# CAN_Sheet.net
KiCad netlist of a schematic drawn in Altium Designer
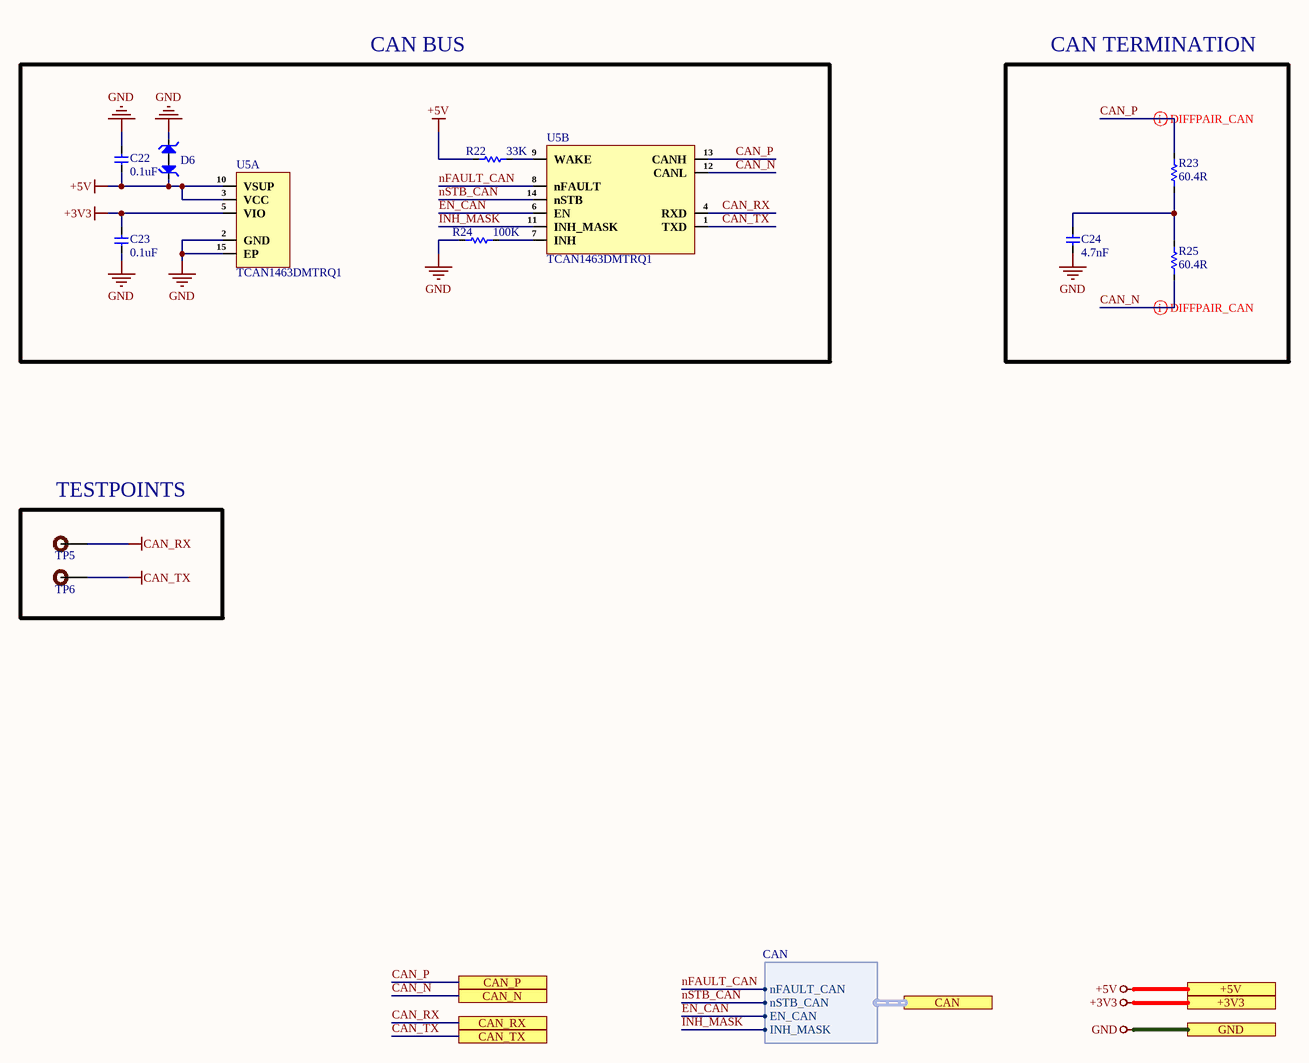
[diagram p0: CAN_Sheet.SchDoc]

(export (version "E")
  (design (tool "Eeschema 10.0.6"))
  (components
    (comp (ref "C22")
      (value "0.1uF")
      (footprint "Cap-0402")
      (description "CAP CER 0.1UF 16V X7R 0402")
      (fields
        (field (name "MANUFACTURER") "Yageo")
        (field (name "MANUFACTURER PART NUMBER") "CC0402JRX7R7BB104")
      )
      (libsource (lib "eSpark Libraries") (part "CC0402JRX7R7BB104"))
    )
    (comp (ref "C23")
      (value "0.1uF")
      (footprint "Cap-0402")
      (description "CAP CER 0.1UF 16V X7R 0402")
      (fields
        (field (name "MANUFACTURER") "Yageo")
        (field (name "MANUFACTURER PART NUMBER") "CC0402JRX7R7BB104")
      )
      (libsource (lib "eSpark Libraries") (part "CC0402JRX7R7BB104"))
    )
    (comp (ref "C24")
      (value "4.7nF")
      (footprint "Cap-0402")
      (description "CAP CER 4700PF 50V X7R 0402")
      (fields
        (field (name "MANUFACTURER") "Yageo")
        (field (name "MANUFACTURER PART NUMBER") "CC0402KRX7R9BB472")
      )
      (libsource (lib "eSpark Libraries") (part "CC0402KRX7R9BB472"))
    )
    (comp (ref "D6")
      (value "PESD5V0H1BSFYL")
      (footprint "DSN0603-2")
      (description "TVS DIODE 5VWM 6.3VC DSN0603-2")
      (fields (field (name "MANUFACTURER") "Nexperia") (field (name "LCSC PART NUMBER") "C477989"))
      (libsource (lib "eSpark Libraries") (part "PESD5V0H1BSFYL"))
    )
    (comp (ref "R22")
      (value "33K")
      (footprint "Res-0402")
      (description "RES 33K OHM 1% 1/16W 0402")
      (fields
        (field (name "MANUFACTURER") "YAGEO")
        (field (name "MANUFACTURER PART NUMBER") "RC0402FR-0733KL")
      )
      (libsource (lib "eSpark Libraries") (part "RC0402FR-0733KL"))
    )
    (comp (ref "R23")
      (value "60.4R")
      (footprint "Res-0603")
      (description "100mW Thick Film Resistors ±100ppm/℃ ±1% 60.4Ω 0603 Chip Resistor - Surface Mount ROHS")
      (fields
        (field (name "MANUFACTURER PART NUMBER") "RTT0360R4FTP")
        (field (name "LCSC PART NUMBER") "C103744")
      )
      (libsource (lib "eSpark Libraries") (part "RTT0360R4FTP"))
    )
    (comp (ref "R24")
      (value "100K")
      (footprint "Res-0402")
      (description "RES 100K OHM 1% 1/16W 0402")
      (fields
        (field (name "MANUFACTURER") "Yageo")
        (field (name "MANUFACTURER PART NUMBER") "RC0402FR-07100KL")
      )
      (libsource (lib "eSpark Libraries") (part "RC0402FR-07100KL"))
    )
    (comp (ref "R25")
      (value "60.4R")
      (footprint "Res-0603")
      (description "100mW Thick Film Resistors ±100ppm/℃ ±1% 60.4Ω 0603 Chip Resistor - Surface Mount ROHS")
      (fields
        (field (name "MANUFACTURER PART NUMBER") "RTT0360R4FTP")
        (field (name "LCSC PART NUMBER") "C103744")
      )
      (libsource (lib "eSpark Libraries") (part "RTT0360R4FTP"))
    )
    (comp (ref "TP5")
      (value "TEST POINT")
      (footprint "Test-point")
      (description "Test Point ON")
      (libsource (lib "eSpark Libraries") (part "TEST POINT"))
    )
    (comp (ref "TP6")
      (value "TEST POINT")
      (footprint "Test-point")
      (description "Test Point ON")
      (libsource (lib "eSpark Libraries") (part "TEST POINT"))
    )
    (comp (ref "U5")
      (value "TCAN1463DMTRQ1")
      (footprint "VSON-14(3x4.5)")
      (description "IC TRANSCEIVER HALF 1/1 14VSON")
      (fields (field (name "MANUFACTURER") "Texas Instruments") (field (name "LCSC PART NUMBER") "C5215823"))
      (libsource (lib "eSpark Libraries") (part "TCAN1463DMTRQ1"))
    )
  )
  (nets
    (net (code "2") (name "+3V3") (class "Default")
      (node (ref "C23") (pin "2") (pinfunction "2_2") (pintype "passive"))
      (node (ref "U5") (pin "5") (pinfunction "VIO_5") (pintype "passive"))
    )
    (net (code "3") (name "+5V") (class "Default")
      (node (ref "C22") (pin "1") (pinfunction "1_1") (pintype "passive"))
      (node (ref "D6") (pin "1") (pinfunction "1_1") (pintype "passive"))
      (node (ref "R22") (pin "1") (pinfunction "1_1") (pintype "passive"))
      (node (ref "U5") (pin "10") (pinfunction "VSUP_10") (pintype "passive"))
      (node (ref "U5") (pin "3") (pinfunction "VCC_3") (pintype "passive"))
    )
    (net (code "4") (name "/CAN_N") (class "Default")
      (node (ref "R25") (pin "2") (pinfunction "2_2") (pintype "passive"))
      (node (ref "U5") (pin "12") (pinfunction "CANL_12") (pintype "passive"))
    )
    (net (code "5") (name "/CAN_P") (class "Default")
      (node (ref "R23") (pin "1") (pinfunction "1_1") (pintype "passive"))
      (node (ref "U5") (pin "13") (pinfunction "CANH_13") (pintype "passive"))
    )
    (net (code "6") (name "/EN_CAN") (class "Default")
      (node (ref "U5") (pin "6") (pinfunction "EN_6") (pintype "passive"))
    )
    (net (code "7") (name "/INH_MASK") (class "Default")
      (node (ref "U5") (pin "11") (pinfunction "INH_MASK_11") (pintype "passive"))
    )
    (net (code "8") (name "/nFAULT_CAN") (class "Default")
      (node (ref "U5") (pin "8") (pinfunction "nFAULT_8") (pintype "passive"))
    )
    (net (code "9") (name "/nSTB_CAN") (class "Default")
      (node (ref "U5") (pin "14") (pinfunction "nSTB_14") (pintype "passive"))
    )
    (net (code "11") (name "CAN_RX") (class "Default")
      (node (ref "TP5") (pin "1") (pinfunction "1_1") (pintype "passive"))
      (node (ref "U5") (pin "4") (pinfunction "RXD_4") (pintype "passive"))
    )
    (net (code "12") (name "CAN_TX") (class "Default")
      (node (ref "TP6") (pin "1") (pinfunction "1_1") (pintype "passive"))
      (node (ref "U5") (pin "1") (pinfunction "TXD_1") (pintype "passive"))
    )
    (net (code "13") (name "GND") (class "Default")
      (node (ref "C22") (pin "2") (pinfunction "2_2") (pintype "passive"))
      (node (ref "C23") (pin "1") (pinfunction "1_1") (pintype "passive"))
      (node (ref "C24") (pin "2") (pinfunction "2_2") (pintype "passive"))
      (node (ref "D6") (pin "2") (pinfunction "2_2") (pintype "passive"))
      (node (ref "R24") (pin "1") (pinfunction "1_1") (pintype "passive"))
      (node (ref "U5") (pin "15") (pinfunction "EP_15") (pintype "passive"))
      (node (ref "U5") (pin "2") (pinfunction "GND_2") (pintype "passive"))
    )
    (net (code "14") (name "Net-(C24-Pad1)") (class "Default")
      (node (ref "C24") (pin "1") (pinfunction "1_1") (pintype "passive"))
      (node (ref "R23") (pin "2") (pinfunction "2_2") (pintype "passive"))
      (node (ref "R25") (pin "1") (pinfunction "1_1") (pintype "passive"))
    )
    (net (code "15") (name "Net-(U5B-INH)") (class "Default")
      (node (ref "R24") (pin "2") (pinfunction "2_2") (pintype "passive"))
      (node (ref "U5") (pin "7") (pinfunction "INH_7") (pintype "passive"))
    )
    (net (code "16") (name "Net-(U5B-WAKE)") (class "Default")
      (node (ref "R22") (pin "2") (pinfunction "2_2") (pintype "passive"))
      (node (ref "U5") (pin "9") (pinfunction "WAKE_9") (pintype "passive"))
    )
  )
)
